# SX1308_GTW_e381v02c_Power.net
KiCad netlist of a schematic drawn in Altium Designer
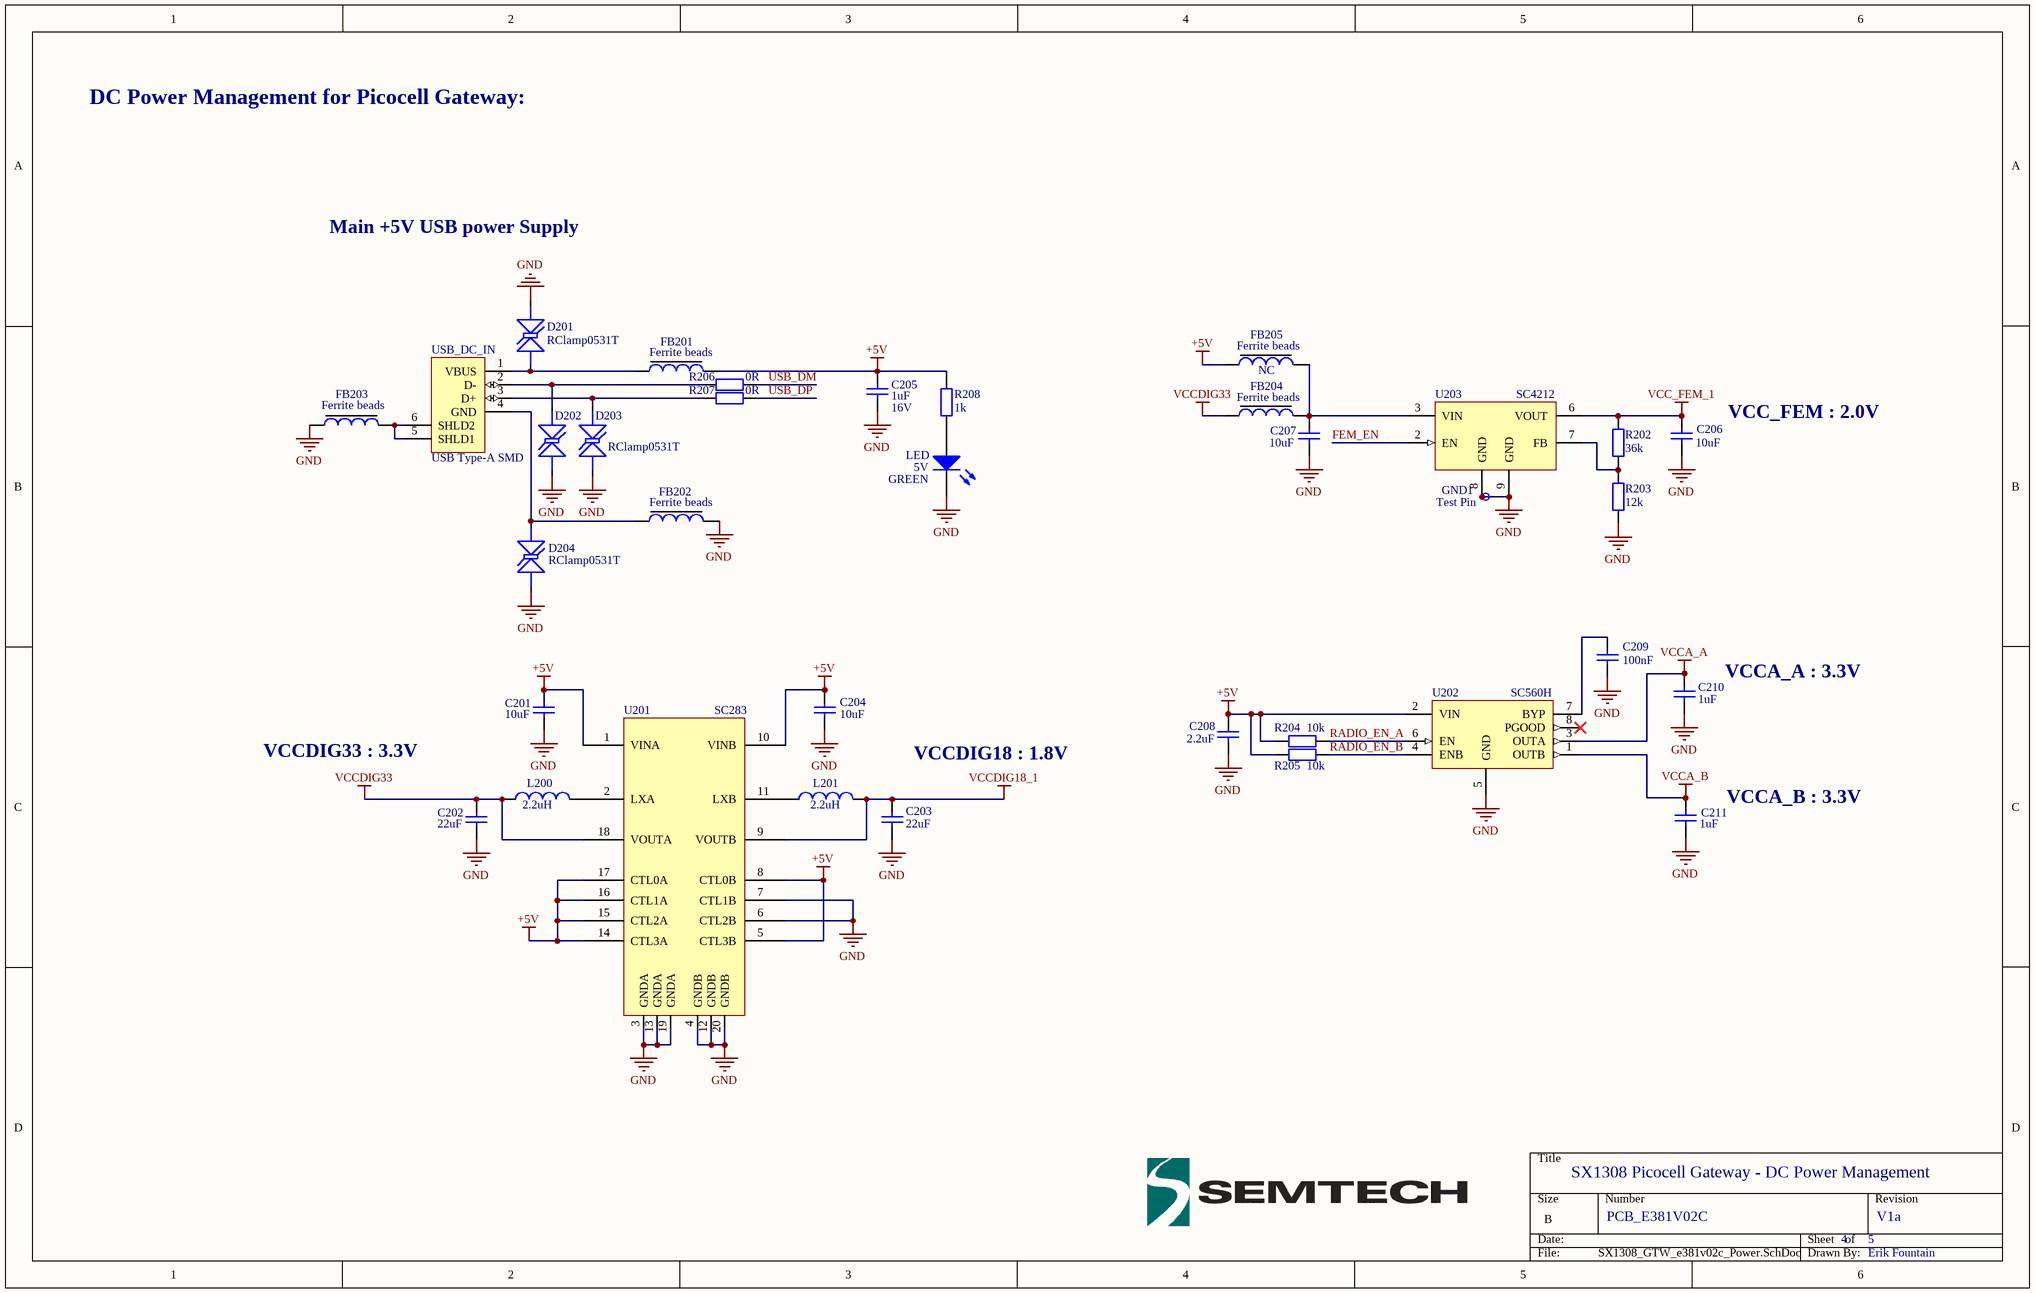
[diagram p0: SX1308_GTW_e381v02c_Power.SchDoc]

(export (version "E")
  (design (tool "Eeschema 10.0.6"))
  (components
    (comp (ref "5V")
      (value "LED")
      (footprint "CD1608-0603")
      (fields (field (name "TYPE") "GREEN"))
      (libsource (lib "SX1308_GTW_e381v02c") (part "LED"))
    )
    (comp (ref "C201")
      (value "10uF")
      (footprint "C1206")
      (description "Capacitor SMD")
      (fields (field (name "Comment") "Cap") (field (name "PUBLISHER") "Altium Limited"))
      (libsource (lib "SX1308_GTW_e381v02c") (part "Cap"))
    )
    (comp (ref "C202")
      (value "22uF")
      (footprint "C1206")
      (description "Capacitor SMD")
      (fields (field (name "Comment") "Cap") (field (name "PUBLISHER") "Altium Limited"))
      (libsource (lib "SX1308_GTW_e381v02c") (part "Cap"))
    )
    (comp (ref "C203")
      (value "22uF")
      (footprint "C1206")
      (description "Capacitor SMD")
      (fields (field (name "Comment") "Cap") (field (name "PUBLISHER") "Altium Limited"))
      (libsource (lib "SX1308_GTW_e381v02c") (part "Cap"))
    )
    (comp (ref "C204")
      (value "10uF")
      (footprint "C1206")
      (description "Capacitor SMD")
      (fields (field (name "Comment") "Cap") (field (name "PUBLISHER") "Altium Limited"))
      (libsource (lib "SX1308_GTW_e381v02c") (part "Cap"))
    )
    (comp (ref "C205")
      (value "1uF")
      (footprint "rlc_805_smd")
      (description "Capacitor SMD")
      (fields
        (field (name "DC VOLTAGE") "16V")
        (field (name "Comment") "Cap")
        (field (name "PUBLISHER") "Altium Limited")
      )
      (libsource (lib "SX1308_GTW_e381v02c") (part "Cap"))
    )
    (comp (ref "C206")
      (value "10uF")
      (footprint "rlc_805_smd")
      (description "Capacitor SMD")
      (fields (field (name "Comment") "Cap") (field (name "PUBLISHER") "Altium Limited"))
      (libsource (lib "SX1308_GTW_e381v02c") (part "Cap"))
    )
    (comp (ref "C207")
      (value "10uF")
      (footprint "rlc_805_smd")
      (description "Capacitor SMD")
      (fields (field (name "Comment") "Cap") (field (name "PUBLISHER") "Altium Limited"))
      (libsource (lib "SX1308_GTW_e381v02c") (part "Cap"))
    )
    (comp (ref "C208")
      (value "2.2uF")
      (footprint "rlc_603_smd")
      (description "Capacitor SMD")
      (fields (field (name "Comment") "Cap") (field (name "PUBLISHER") "Altium Limited"))
      (libsource (lib "SX1308_GTW_e381v02c") (part "Cap"))
    )
    (comp (ref "C209")
      (value "100nF")
      (footprint "rlc_402_smd")
      (description "Capacitor SMD")
      (fields (field (name "Comment") "Cap") (field (name "PUBLISHER") "Altium Limited"))
      (libsource (lib "SX1308_GTW_e381v02c") (part "Cap"))
    )
    (comp (ref "C210")
      (value "1uF")
      (footprint "rlc_805_smd")
      (description "Capacitor SMD")
      (fields (field (name "Comment") "Cap") (field (name "PUBLISHER") "Altium Limited"))
      (libsource (lib "SX1308_GTW_e381v02c") (part "Cap"))
    )
    (comp (ref "C211")
      (value "1uF")
      (footprint "rlc_805_smd")
      (description "Capacitor SMD")
      (fields (field (name "Comment") "Cap") (field (name "PUBLISHER") "Altium Limited"))
      (libsource (lib "SX1308_GTW_e381v02c") (part "Cap"))
    )
    (comp (ref "D201")
      (value "RClamp0531T")
      (footprint "SLP1006P2T")
      (description "Ultra Low Capacitance 1-line ESD Protection")
      (fields (field (name "TYPE") "RClamp0531T"))
      (libsource (lib "SX1308_GTW_e381v02c") (part "RClamp0531T"))
    )
    (comp (ref "D202")
      (value "RClamp0531T")
      (footprint "SLP1006P2T")
      (description "Ultra Low Capacitance 1-line ESD Protection")
      (libsource (lib "SX1308_GTW_e381v02c") (part "RClamp0531T"))
    )
    (comp (ref "D203")
      (value "RClamp0531T")
      (footprint "SLP1006P2T")
      (description "Ultra Low Capacitance 1-line ESD Protection")
      (fields (field (name "TYPE") "RClamp0531T"))
      (libsource (lib "SX1308_GTW_e381v02c") (part "RClamp0531T"))
    )
    (comp (ref "D204")
      (value "RClamp0531T")
      (footprint "SLP1006P2T")
      (description "Ultra Low Capacitance 1-line ESD Protection")
      (fields (field (name "TYPE") "RClamp0531T"))
      (libsource (lib "SX1308_GTW_e381v02c") (part "RClamp0531T"))
    )
    (comp (ref "FB201")
      (value "Ferrite beads")
      (footprint "rlc_402_smd")
      (libsource (lib "SX1308_GTW_e381v02c") (part "Ferrite beads"))
    )
    (comp (ref "FB202")
      (value "Ferrite beads")
      (footprint "rlc_402_smd")
      (libsource (lib "SX1308_GTW_e381v02c") (part "Ferrite beads"))
    )
    (comp (ref "FB203")
      (value "Ferrite beads")
      (footprint "rlc_402_smd")
      (libsource (lib "SX1308_GTW_e381v02c") (part "Ferrite beads"))
    )
    (comp (ref "FB204")
      (value "Ferrite beads")
      (footprint "rlc_402_smd")
      (libsource (lib "SX1308_GTW_e381v02c") (part "Ferrite beads"))
    )
    (comp (ref "FB205")
      (value "Ferrite beads")
      (footprint "rlc_402_smd")
      (fields (field (name "ALTIUM_VALUE") "NC"))
      (libsource (lib "SX1308_GTW_e381v02c") (part "Ferrite beads"))
    )
    (comp (ref "GND1")
      (value "Test Pin")
      (footprint "pin_1mm")
      (libsource (lib "SX1308_GTW_e381v02c") (part "test_pin"))
    )
    (comp (ref "L200")
      (value "2.2uH")
      (footprint "L4818")
      (description "Inductor")
      (fields (field (name "PUBLISHER") "Altium Limited"))
      (libsource (lib "SX1308_GTW_e381v02c") (part "Inductor"))
    )
    (comp (ref "L201")
      (value "2.2uH")
      (footprint "L4818")
      (description "Inductor")
      (fields (field (name "PUBLISHER") "Altium Limited"))
      (libsource (lib "SX1308_GTW_e381v02c") (part "Inductor"))
    )
    (comp (ref "R202")
      (value "36k")
      (footprint "rlc_402_smd")
      (description "Resistor SMD - IEC symbol version")
      (fields (field (name "Comment") "Resistor"))
      (libsource (lib "") (part "Resistor_1"))
    )
    (comp (ref "R203")
      (value "12k")
      (footprint "rlc_402_smd")
      (description "Resistor SMD - IEC symbol version")
      (fields (field (name "Comment") "Resistor"))
      (libsource (lib "") (part "Resistor_1"))
    )
    (comp (ref "R204")
      (value "10k")
      (footprint "rlc_402_smd")
      (description "Resistor SMD - IEC symbol version")
      (fields (field (name "Comment") "Resistor"))
      (libsource (lib "SX1308_GTW_e381v02c") (part "Resistor"))
    )
    (comp (ref "R205")
      (value "10k")
      (footprint "rlc_402_smd")
      (description "Resistor SMD - IEC symbol version")
      (fields (field (name "Comment") "Resistor"))
      (libsource (lib "SX1308_GTW_e381v02c") (part "Resistor"))
    )
    (comp (ref "R206")
      (value "0R")
      (footprint "rlc_402_smd")
      (description "Resistor SMD - IEC symbol version")
      (fields (field (name "Comment") "Resistor"))
      (libsource (lib "SX1308_GTW_e381v02c") (part "Resistor"))
    )
    (comp (ref "R207")
      (value "0R")
      (footprint "rlc_402_smd")
      (description "Resistor SMD - IEC symbol version")
      (fields (field (name "Comment") "Resistor"))
      (libsource (lib "SX1308_GTW_e381v02c") (part "Resistor"))
    )
    (comp (ref "R208")
      (value "1k")
      (footprint "rlc_402_smd")
      (description "Resistor SMD - IEC symbol version")
      (fields (field (name "Comment") "Resistor"))
      (libsource (lib "") (part "Resistor_1"))
    )
    (comp (ref "U201")
      (value "SC283")
      (footprint "MLPQ-W18")
      (description "SC283 - Dual Channel 2.5MHz, 1.8A  Synchronous Step-Down Regulator")
      (libsource (lib "SX1308_GTW_e381v02c") (part "SC283"))
    )
    (comp (ref "U202")
      (value "SC560H")
      (footprint "MLPQ-UT8")
      (description "SC560H - Dual Output Low Noise LDO  Linear Regulator")
      (libsource (lib "SX1308_GTW_e381v02c") (part "SC560H"))
    )
    (comp (ref "U203")
      (value "SC4212")
      (footprint "MLPD-8 3x3mm")
      (description "SC4212 - Very Low Input /Very Low Dropout  1Amp Regulator With Enable")
      (libsource (lib "SX1308_GTW_e381v02c") (part "SC4212"))
    )
    (comp (ref "USB_DC_IN")
      (value "USB Type-A SMD")
      (footprint "Keystone USB Type 931")
      (description "USB 2.0 SMT, Type A, Receptacle, 4 Position")
      (libsource (lib "SX1308_GTW_e381v02c") (part "USB Type-A SMD"))
    )
  )
  (nets
    (net (code "1") (name "+5V") (class "Default")
      (node (ref "C201") (pin "1") (pinfunction "1_1") (pintype "passive"))
      (node (ref "C204") (pin "1") (pinfunction "1_1") (pintype "passive"))
      (node (ref "C205") (pin "1") (pinfunction "1_1") (pintype "passive"))
      (node (ref "C208") (pin "1") (pinfunction "1_1") (pintype "passive"))
      (node (ref "FB201") (pin "2") (pinfunction "2_2") (pintype "passive"))
      (node (ref "FB205") (pin "1") (pinfunction "1_1") (pintype "passive"))
      (node (ref "R204") (pin "1") (pinfunction "1_1") (pintype "passive"))
      (node (ref "R205") (pin "1") (pinfunction "1_1") (pintype "passive"))
      (node (ref "R208") (pin "1") (pinfunction "1_1") (pintype "passive"))
      (node (ref "U201") (pin "1") (pinfunction "VINA_1") (pintype "passive"))
      (node (ref "U201") (pin "10") (pinfunction "VINB_10") (pintype "passive"))
      (node (ref "U201") (pin "14") (pinfunction "CTL3A_14") (pintype "passive"))
      (node (ref "U201") (pin "15") (pinfunction "CTL2A_15") (pintype "passive"))
      (node (ref "U201") (pin "16") (pinfunction "CTL1A_16") (pintype "passive"))
      (node (ref "U201") (pin "17") (pinfunction "CTL0A_17") (pintype "passive"))
      (node (ref "U201") (pin "5") (pinfunction "CTL3B_5") (pintype "passive"))
      (node (ref "U201") (pin "8") (pinfunction "CTL0B_8") (pintype "passive"))
      (node (ref "U202") (pin "2") (pinfunction "VIN_2") (pintype "passive"))
    )
    (net (code "2") (name "/FEM_EN") (class "Default")
      (node (ref "U203") (pin "2") (pinfunction "EN_2") (pintype "input"))
    )
    (net (code "3") (name "/RADIO_EN_A") (class "Default")
      (node (ref "R204") (pin "2") (pinfunction "2_2") (pintype "passive"))
      (node (ref "U202") (pin "6") (pinfunction "EN_6") (pintype "input"))
    )
    (net (code "4") (name "/RADIO_EN_B") (class "Default")
      (node (ref "R205") (pin "2") (pinfunction "2_2") (pintype "passive"))
      (node (ref "U202") (pin "4") (pinfunction "ENB_4") (pintype "passive"))
    )
    (net (code "5") (name "/USB_DM") (class "Default")
      (node (ref "R206") (pin "2") (pinfunction "2_2") (pintype "passive"))
    )
    (net (code "6") (name "/USB_DP") (class "Default")
      (node (ref "R207") (pin "2") (pinfunction "2_2") (pintype "passive"))
    )
    (net (code "7") (name "GND") (class "Default")
      (node (ref "5V") (pin "2") (pinfunction "K_2") (pintype "passive"))
      (node (ref "C201") (pin "2") (pinfunction "2_2") (pintype "passive"))
      (node (ref "C202") (pin "2") (pinfunction "2_2") (pintype "passive"))
      (node (ref "C203") (pin "2") (pinfunction "2_2") (pintype "passive"))
      (node (ref "C204") (pin "2") (pinfunction "2_2") (pintype "passive"))
      (node (ref "C205") (pin "2") (pinfunction "2_2") (pintype "passive"))
      (node (ref "C206") (pin "2") (pinfunction "2_2") (pintype "passive"))
      (node (ref "C207") (pin "2") (pinfunction "2_2") (pintype "passive"))
      (node (ref "C208") (pin "2") (pinfunction "2_2") (pintype "passive"))
      (node (ref "C209") (pin "1") (pinfunction "1_1") (pintype "passive"))
      (node (ref "C210") (pin "2") (pinfunction "2_2") (pintype "passive"))
      (node (ref "C211") (pin "2") (pinfunction "2_2") (pintype "passive"))
      (node (ref "D201") (pin "2") (pinfunction "K_2") (pintype "passive"))
      (node (ref "D202") (pin "2") (pinfunction "K_2") (pintype "passive"))
      (node (ref "D203") (pin "2") (pinfunction "K_2") (pintype "passive"))
      (node (ref "D204") (pin "2") (pinfunction "K_2") (pintype "passive"))
      (node (ref "FB202") (pin "2") (pinfunction "2_2") (pintype "passive"))
      (node (ref "FB203") (pin "1") (pinfunction "1_1") (pintype "passive"))
      (node (ref "GND1") (pin "1") (pinfunction "pin_1") (pintype "passive"))
      (node (ref "R203") (pin "2") (pinfunction "2_2") (pintype "passive"))
      (node (ref "U201") (pin "12") (pinfunction "GNDB_12") (pintype "passive"))
      (node (ref "U201") (pin "13") (pinfunction "GNDA_13") (pintype "passive"))
      (node (ref "U201") (pin "19") (pinfunction "GNDA_19") (pintype "passive"))
      (node (ref "U201") (pin "20") (pinfunction "GNDB_20") (pintype "passive"))
      (node (ref "U201") (pin "3") (pinfunction "GNDA_3") (pintype "passive"))
      (node (ref "U201") (pin "4") (pinfunction "GNDB_4") (pintype "passive"))
      (node (ref "U201") (pin "6") (pinfunction "CTL2B_6") (pintype "passive"))
      (node (ref "U201") (pin "7") (pinfunction "CTL1B_7") (pintype "passive"))
      (node (ref "U202") (pin "5") (pinfunction "GND_5") (pintype "power_in"))
      (node (ref "U203") (pin "8") (pinfunction "GND_8") (pintype "power_in"))
      (node (ref "U203") (pin "9") (pinfunction "GND_9") (pintype "power_in"))
    )
    (net (code "8") (name "Net-(5V-A)") (class "Default")
      (node (ref "5V") (pin "1") (pinfunction "A_1") (pintype "passive"))
      (node (ref "R208") (pin "2") (pinfunction "2_2") (pintype "passive"))
    )
    (net (code "9") (name "Net-(D201-A)") (class "Default")
      (node (ref "D201") (pin "1") (pinfunction "A_1") (pintype "passive"))
      (node (ref "FB201") (pin "1") (pinfunction "1_1") (pintype "passive"))
      (node (ref "USB_DC_IN") (pin "1") (pinfunction "VBUS_1") (pintype "power_in"))
    )
    (net (code "10") (name "Net-(D202-A)") (class "Default")
      (node (ref "D202") (pin "1") (pinfunction "A_1") (pintype "passive"))
      (node (ref "R206") (pin "1") (pinfunction "1_1") (pintype "passive"))
      (node (ref "USB_DC_IN") (pin "2") (pinfunction "D-_2") (pintype "bidirectional"))
    )
    (net (code "11") (name "Net-(D203-A)") (class "Default")
      (node (ref "D203") (pin "1") (pinfunction "A_1") (pintype "passive"))
      (node (ref "R207") (pin "1") (pinfunction "1_1") (pintype "passive"))
      (node (ref "USB_DC_IN") (pin "3") (pinfunction "D+_3") (pintype "bidirectional"))
    )
    (net (code "12") (name "Net-(D204-A)") (class "Default")
      (node (ref "D204") (pin "1") (pinfunction "A_1") (pintype "passive"))
      (node (ref "FB202") (pin "1") (pinfunction "1_1") (pintype "passive"))
      (node (ref "USB_DC_IN") (pin "4") (pinfunction "GND_4") (pintype "power_in"))
    )
    (net (code "13") (name "Net-(U201-LXA)") (class "Default")
      (node (ref "L200") (pin "2") (pinfunction "2_2") (pintype "passive"))
      (node (ref "U201") (pin "2") (pinfunction "LXA_2") (pintype "passive"))
    )
    (net (code "14") (name "Net-(U201-LXB)") (class "Default")
      (node (ref "L201") (pin "1") (pinfunction "1_1") (pintype "passive"))
      (node (ref "U201") (pin "11") (pinfunction "LXB_11") (pintype "passive"))
    )
    (net (code "15") (name "Net-(U202-BYP)") (class "Default")
      (node (ref "C209") (pin "2") (pinfunction "2_2") (pintype "passive"))
      (node (ref "U202") (pin "7") (pinfunction "BYP_7") (pintype "passive"))
    )
    (net (code "16") (name "Net-(U203-FB)") (class "Default")
      (node (ref "R202") (pin "2") (pinfunction "2_2") (pintype "passive"))
      (node (ref "R203") (pin "1") (pinfunction "1_1") (pintype "passive"))
      (node (ref "U203") (pin "7") (pinfunction "FB_7") (pintype "passive"))
    )
    (net (code "17") (name "Net-(U203-VIN)") (class "Default")
      (node (ref "C207") (pin "1") (pinfunction "1_1") (pintype "passive"))
      (node (ref "FB204") (pin "2") (pinfunction "2_2") (pintype "passive"))
      (node (ref "FB205") (pin "2") (pinfunction "2_2") (pintype "passive"))
      (node (ref "U203") (pin "3") (pinfunction "VIN_3") (pintype "passive"))
    )
    (net (code "18") (name "Net-(USB_DC_IN-SHLD1)") (class "Default")
      (node (ref "FB203") (pin "2") (pinfunction "2_2") (pintype "passive"))
      (node (ref "USB_DC_IN") (pin "5") (pinfunction "SHLD1_5") (pintype "power_in"))
      (node (ref "USB_DC_IN") (pin "6") (pinfunction "SHLD2_6") (pintype "power_in"))
    )
    (net (code "19") (name "VCCA_A") (class "Default")
      (node (ref "C210") (pin "1") (pinfunction "1_1") (pintype "passive"))
      (node (ref "U202") (pin "3") (pinfunction "OUTA_3") (pintype "output"))
    )
    (net (code "20") (name "VCCA_B") (class "Default")
      (node (ref "C211") (pin "1") (pinfunction "1_1") (pintype "passive"))
      (node (ref "U202") (pin "1") (pinfunction "OUTB_1") (pintype "output"))
    )
    (net (code "21") (name "VCCDIG18_1") (class "Default")
      (node (ref "C203") (pin "1") (pinfunction "1_1") (pintype "passive"))
      (node (ref "L201") (pin "2") (pinfunction "2_2") (pintype "passive"))
      (node (ref "U201") (pin "9") (pinfunction "VOUTB_9") (pintype "passive"))
    )
    (net (code "22") (name "VCCDIG33") (class "Default")
      (node (ref "C202") (pin "1") (pinfunction "1_1") (pintype "passive"))
      (node (ref "FB204") (pin "1") (pinfunction "1_1") (pintype "passive"))
      (node (ref "L200") (pin "1") (pinfunction "1_1") (pintype "passive"))
      (node (ref "U201") (pin "18") (pinfunction "VOUTA_18") (pintype "passive"))
    )
    (net (code "23") (name "VCC_FEM_1") (class "Default")
      (node (ref "C206") (pin "1") (pinfunction "1_1") (pintype "passive"))
      (node (ref "R202") (pin "1") (pinfunction "1_1") (pintype "passive"))
      (node (ref "U203") (pin "6") (pinfunction "VOUT_6") (pintype "passive"))
    )
    (net (code "24") (name "unconnected-(U202-PGOOD-Pad8)") (class "Default")
      (node (ref "U202") (pin "8") (pinfunction "PGOOD_8") (pintype "output+no_connect"))
    )
  )
)
